# chatGPTInterlock.net
KiCad netlist of a schematic drawn in Altium Designer
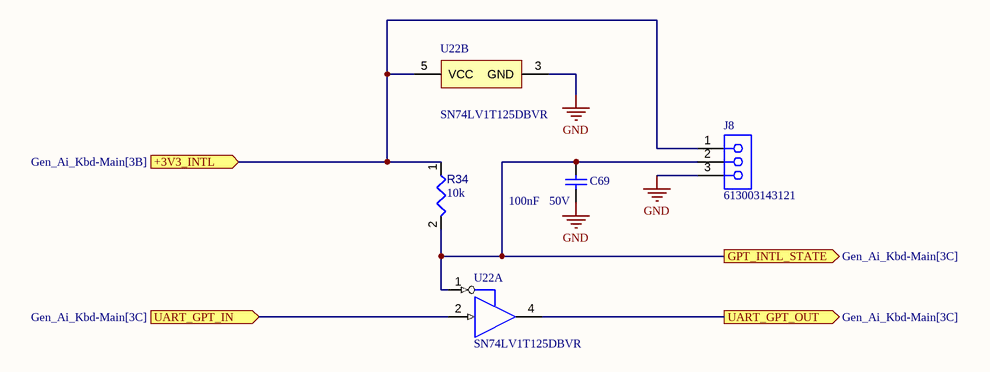
[diagram p0: chatGPTInterlock.SchDoc]

(export (version "E")
  (design (tool "Eeschema 10.0.6"))
  (components
    (comp (ref "C69")
      (value "885012206095")
      (footprint "WCAP-CSGP_0603_L1.6W0.8H0.8_Reflow")
      (description "WCAP-CSGP Multilayer Ceramic Chip Capacitor, General Purpose, size 0603, X7R, 100nF, 50VDC")
      (fields
        (field (name "CAPACITANCE") "100nF")
        (field (name "MANUFACTURER") "Wurth Elektronik")
        (field (name "RATED VOLTAGE (DC)") "50V")
      )
      (libsource (lib "Test365") (part "885012209047R"))
    )
    (comp (ref "J8")
      (value "613003143121")
      (footprint "613003143121")
      (libsource (lib "Altium Content Vault") (part "Header_Female_1R_03P"))
    )
    (comp (ref "R34")
      (value "10k")
      (footprint "RESC1608X55X25ML10T15")
      (description "Chip Resistor, 10 KOhm, +/- 1%, 01 W, -55 to 155 degC, 0603 (1608 Metric)")
      (fields (field (name "POWER") "100mW") (field (name "TOLERANCE") "1%"))
      (libsource (lib "Test365") (part "RES-2"))
    )
    (comp (ref "U22")
      (value "SN74LV1T125DBVR")
      (footprint "DBV0005A_M")
      (description "Single Power Supply, Single BUFFER GATE w/ 3-State Output (active low enable), DBV0005A, LARGE T&R")
      (fields
        (field (name "GENERIC PART NUMBER") "SN74LV1T125")
        (field (name "MANUFACTURER") "Texas Instruments")
      )
      (libsource (lib "Altium Content Vault") (part "TI-SN74AXXXX1X125-5"))
    )
  )
  (nets
    (net (code "1") (name "/+3V3_INTL") (class "Default")
      (node (ref "J8") (pin "1") (pinfunction "1_1") (pintype "passive"))
      (node (ref "R34") (pin "1") (pinfunction "1_1") (pintype "passive"))
      (node (ref "U22") (pin "5") (pinfunction "VCC_5") (pintype "power_in"))
    )
    (net (code "2") (name "/GPT_INTL_STATE") (class "Default")
      (node (ref "C69") (pin "2") (pinfunction "2_2") (pintype "passive"))
      (node (ref "J8") (pin "2") (pinfunction "2_2") (pintype "passive"))
      (node (ref "R34") (pin "2") (pinfunction "2_2") (pintype "passive"))
      (node (ref "U22") (pin "1") (pinfunction "~{OE}_1") (pintype "input"))
    )
    (net (code "3") (name "/UART_GPT_IN") (class "Default")
      (node (ref "U22") (pin "2") (pinfunction "A_2") (pintype "input"))
    )
    (net (code "4") (name "/UART_GPT_OUT") (class "Default")
      (node (ref "U22") (pin "4") (pinfunction "Y_4") (pintype "tri_state"))
    )
    (net (code "5") (name "GND") (class "Default")
      (node (ref "C69") (pin "1") (pinfunction "1_1") (pintype "passive"))
      (node (ref "J8") (pin "3") (pinfunction "3_3") (pintype "passive"))
      (node (ref "U22") (pin "3") (pinfunction "GND_3") (pintype "power_in"))
    )
  )
)
